# GSM_Output_Port.net
KiCad netlist of a schematic drawn in Altium Designer
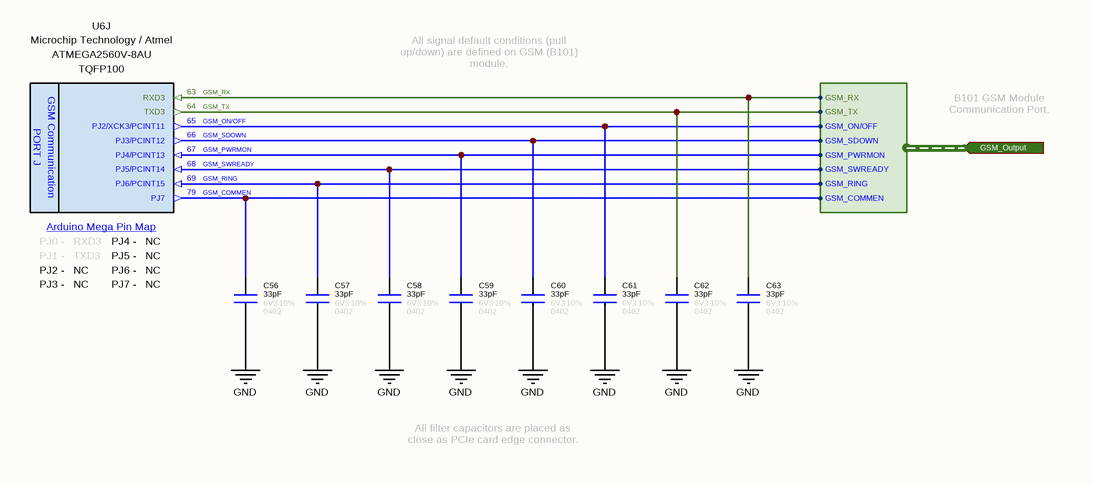
[diagram p0: GSM Output Port.SchDoc]

(export (version "E")
  (design (tool "Eeschema 10.0.6"))
  (components
    (comp (ref "C56")
      (value "33pF")
      (footprint "CAPACITOR_0402")
      (description "Capacitor - 33pF [0402] (Ceramic)")
      (fields
        (field (name "MANUFACTURER PART NUMBER") "C0402C330J9RACAUTO")
        (field (name "TOLERANCE") "10%")
        (field (name "CASE") "0402")
        (field (name "VOLTAGE") "6V3")
      )
      (libsource (lib "P101DA_Library") (part "Capacitor - 33pF [0402-6V3]"))
    )
    (comp (ref "C57")
      (value "33pF")
      (footprint "CAPACITOR_0402")
      (description "Capacitor - 33pF [0402] (Ceramic)")
      (fields
        (field (name "MANUFACTURER PART NUMBER") "C0402C330J9RACAUTO")
        (field (name "TOLERANCE") "10%")
        (field (name "CASE") "0402")
        (field (name "VOLTAGE") "6V3")
      )
      (libsource (lib "P101DA_Library") (part "Capacitor - 33pF [0402-6V3]"))
    )
    (comp (ref "C58")
      (value "33pF")
      (footprint "CAPACITOR_0402")
      (description "Capacitor - 33pF [0402] (Ceramic)")
      (fields
        (field (name "MANUFACTURER PART NUMBER") "C0402C330J9RACAUTO")
        (field (name "TOLERANCE") "10%")
        (field (name "CASE") "0402")
        (field (name "VOLTAGE") "6V3")
      )
      (libsource (lib "P101DA_Library") (part "Capacitor - 33pF [0402-6V3]"))
    )
    (comp (ref "C59")
      (value "33pF")
      (footprint "CAPACITOR_0402")
      (description "Capacitor - 33pF [0402] (Ceramic)")
      (fields
        (field (name "MANUFACTURER PART NUMBER") "C0402C330J9RACAUTO")
        (field (name "TOLERANCE") "10%")
        (field (name "CASE") "0402")
        (field (name "VOLTAGE") "6V3")
      )
      (libsource (lib "P101DA_Library") (part "Capacitor - 33pF [0402-6V3]"))
    )
    (comp (ref "C60")
      (value "33pF")
      (footprint "CAPACITOR_0402")
      (description "Capacitor - 33pF [0402] (Ceramic)")
      (fields
        (field (name "MANUFACTURER PART NUMBER") "C0402C330J9RACAUTO")
        (field (name "TOLERANCE") "10%")
        (field (name "CASE") "0402")
        (field (name "VOLTAGE") "6V3")
      )
      (libsource (lib "P101DA_Library") (part "Capacitor - 33pF [0402-6V3]"))
    )
    (comp (ref "C61")
      (value "33pF")
      (footprint "CAPACITOR_0402")
      (description "Capacitor - 33pF [0402] (Ceramic)")
      (fields
        (field (name "MANUFACTURER PART NUMBER") "C0402C330J9RACAUTO")
        (field (name "TOLERANCE") "10%")
        (field (name "CASE") "0402")
        (field (name "VOLTAGE") "6V3")
      )
      (libsource (lib "P101DA_Library") (part "Capacitor - 33pF [0402-6V3]"))
    )
    (comp (ref "C62")
      (value "33pF")
      (footprint "CAPACITOR_0402")
      (description "Capacitor - 33pF [0402] (Ceramic)")
      (fields
        (field (name "MANUFACTURER PART NUMBER") "C0402C330J9RACAUTO")
        (field (name "TOLERANCE") "10%")
        (field (name "CASE") "0402")
        (field (name "VOLTAGE") "6V3")
      )
      (libsource (lib "P101DA_Library") (part "Capacitor - 33pF [0402-6V3]"))
    )
    (comp (ref "C63")
      (value "33pF")
      (footprint "CAPACITOR_0402")
      (description "Capacitor - 33pF [0402] (Ceramic)")
      (fields
        (field (name "MANUFACTURER PART NUMBER") "C0402C330J9RACAUTO")
        (field (name "TOLERANCE") "10%")
        (field (name "CASE") "0402")
        (field (name "VOLTAGE") "6V3")
      )
      (libsource (lib "P101DA_Library") (part "Capacitor - 33pF [0402-6V3]"))
    )
    (comp (ref "U6")
      (value "ATMEGA2560V-8AU")
      (footprint "TQFP-100")
      (description "ATmega Series 256 KB Flash 8 KB SRAM 8 MHz 8-Bit Microcontroller - TQFP-100")
      (fields
        (field (name "MANUFACTURER NAME") "Microchip Technology / Atmel")
        (field (name "MANUFACTURER PART NUMBER") "ATMEGA2560V-8AU")
        (field (name "CASE") "TQFP100")
      )
      (libsource (lib "P101DA_Library") (part "IC - AtMega2560V-8AU"))
    )
  )
  (nets
    (net (code "2") (name "/GSM_COMMEN") (class "Default")
      (node (ref "C56") (pin "2") (pinfunction "2_2") (pintype "passive"))
      (node (ref "U6") (pin "79") (pinfunction "PJ7_79") (pintype "output"))
    )
    (net (code "3") (name "/GSM_ON{slash}OFF") (class "Default")
      (node (ref "C61") (pin "2") (pinfunction "2_2") (pintype "passive"))
      (node (ref "U6") (pin "65") (pinfunction "PJ2/XCK3/PCINT11_65") (pintype "output"))
    )
    (net (code "4") (name "/GSM_PWRMON") (class "Default")
      (node (ref "C59") (pin "2") (pinfunction "2_2") (pintype "passive"))
      (node (ref "U6") (pin "67") (pinfunction "PJ4/PCINT13_67") (pintype "input"))
    )
    (net (code "5") (name "/GSM_RING") (class "Default")
      (node (ref "C57") (pin "2") (pinfunction "2_2") (pintype "passive"))
      (node (ref "U6") (pin "69") (pinfunction "PJ6/PCINT15_69") (pintype "input"))
    )
    (net (code "6") (name "/GSM_RX") (class "Default")
      (node (ref "C63") (pin "2") (pinfunction "2_2") (pintype "passive"))
      (node (ref "U6") (pin "63") (pinfunction "RXD3_63") (pintype "input"))
    )
    (net (code "7") (name "/GSM_SDOWN") (class "Default")
      (node (ref "C60") (pin "2") (pinfunction "2_2") (pintype "passive"))
      (node (ref "U6") (pin "66") (pinfunction "PJ3/PCINT12_66") (pintype "output"))
    )
    (net (code "8") (name "/GSM_SWREADY") (class "Default")
      (node (ref "C58") (pin "2") (pinfunction "2_2") (pintype "passive"))
      (node (ref "U6") (pin "68") (pinfunction "PJ5/PCINT14_68") (pintype "input"))
    )
    (net (code "9") (name "/GSM_TX") (class "Default")
      (node (ref "C62") (pin "2") (pinfunction "2_2") (pintype "passive"))
      (node (ref "U6") (pin "64") (pinfunction "TXD3_64") (pintype "output"))
    )
    (net (code "11") (name "GND") (class "Default")
      (node (ref "C56") (pin "1") (pinfunction "1_1") (pintype "passive"))
      (node (ref "C57") (pin "1") (pinfunction "1_1") (pintype "passive"))
      (node (ref "C58") (pin "1") (pinfunction "1_1") (pintype "passive"))
      (node (ref "C59") (pin "1") (pinfunction "1_1") (pintype "passive"))
      (node (ref "C60") (pin "1") (pinfunction "1_1") (pintype "passive"))
      (node (ref "C61") (pin "1") (pinfunction "1_1") (pintype "passive"))
      (node (ref "C62") (pin "1") (pinfunction "1_1") (pintype "passive"))
      (node (ref "C63") (pin "1") (pinfunction "1_1") (pintype "passive"))
    )
  )
)
